# BUJT13-VN02-20140328.net
KiCad netlist of a schematic drawn in Altium Designer
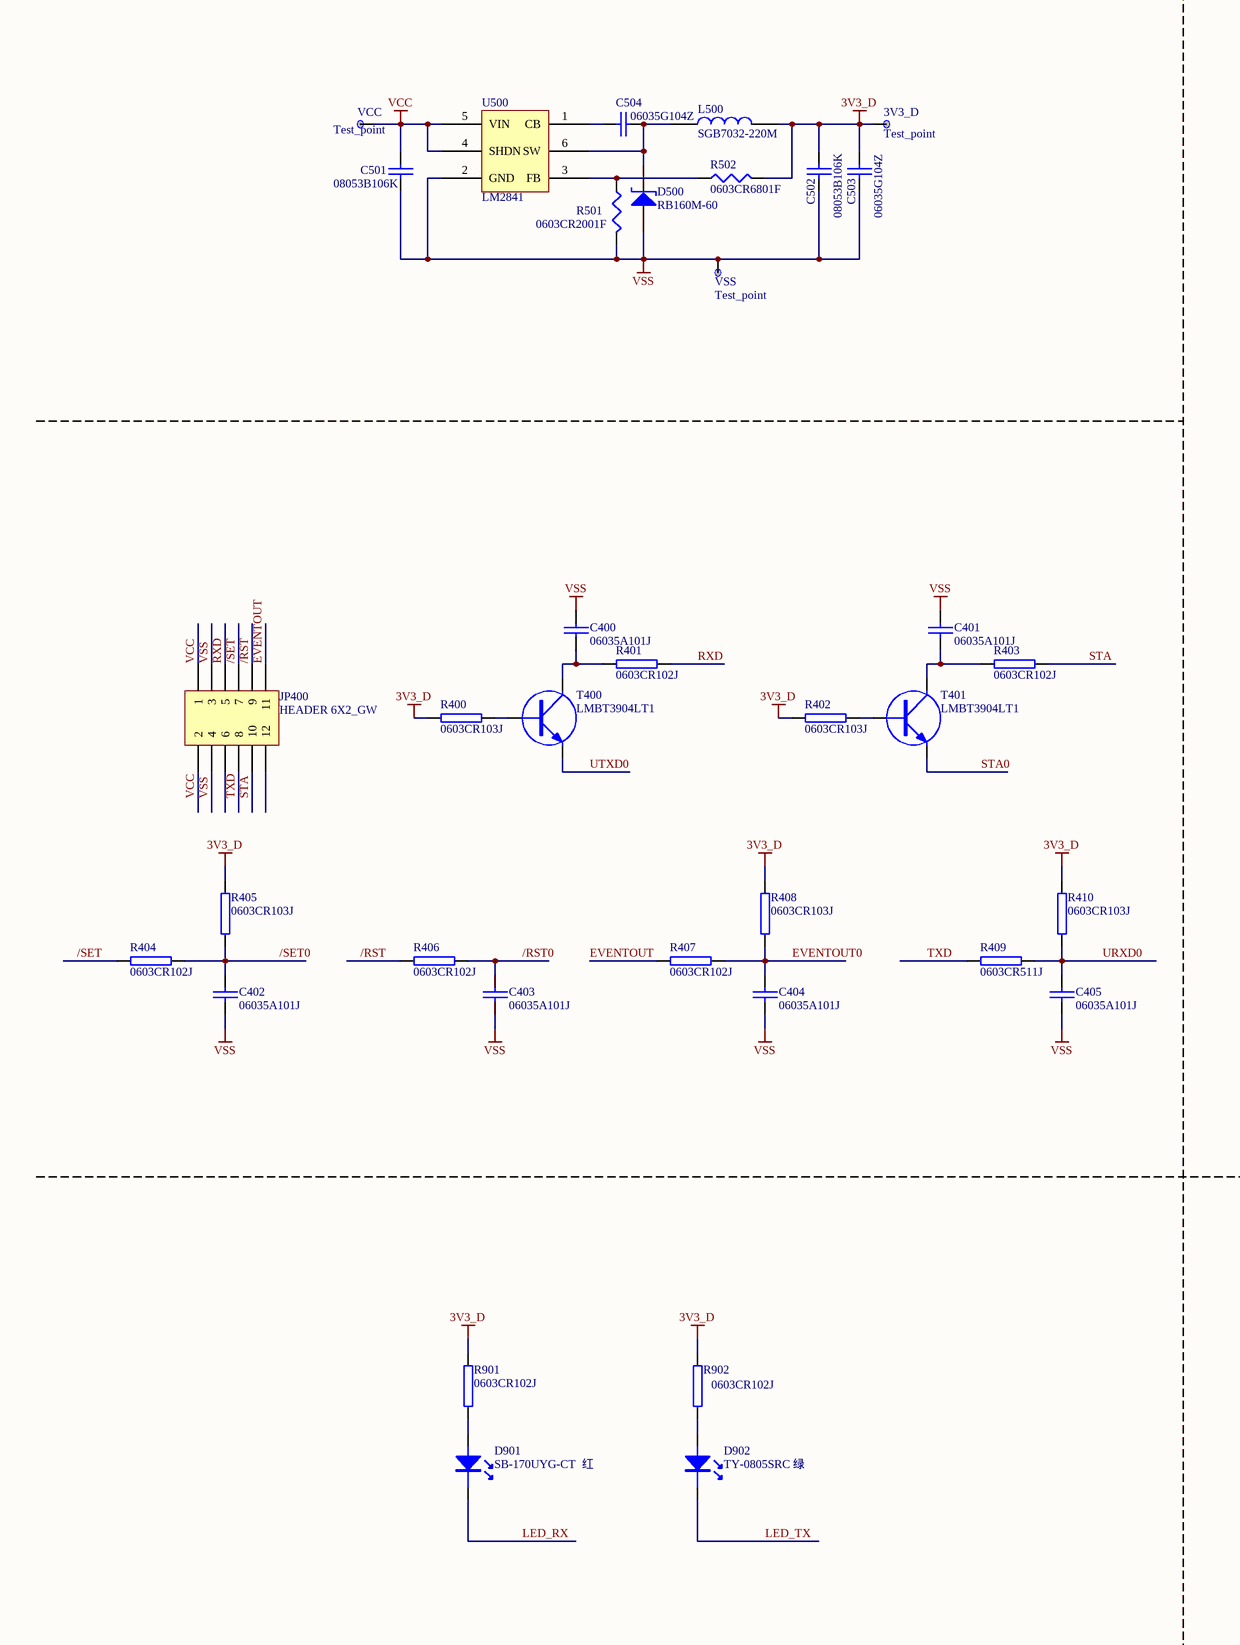
[diagram p0: BUJT13-VN02-20140328.SchDoc, left]
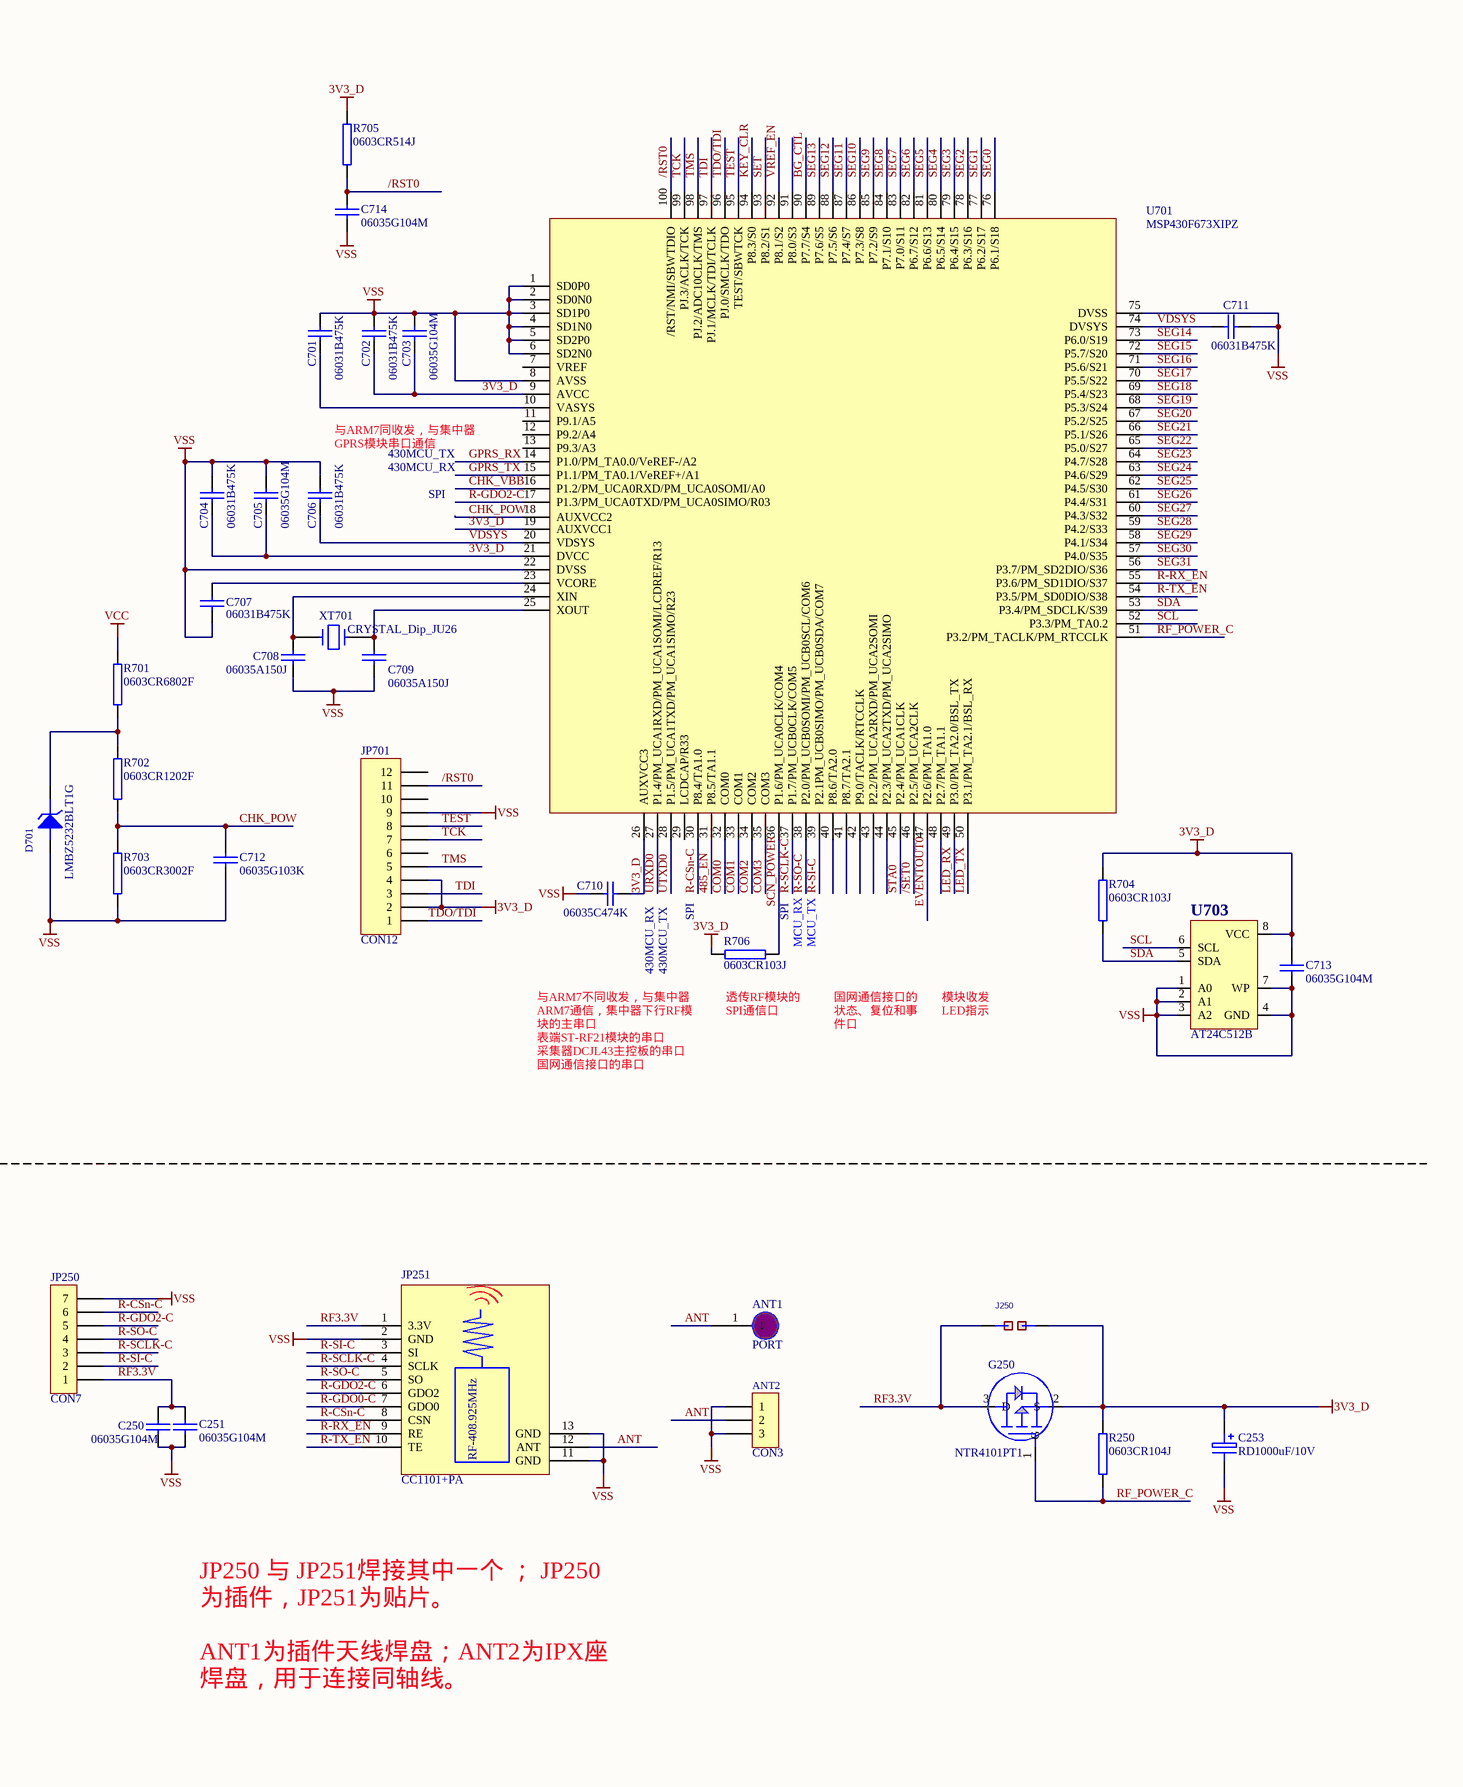
[diagram p1: BUJT13-VN02-20140328.SchDoc, right]

(export (version "E")
  (design (tool "Eeschema 10.0.6"))
  (components
    (comp (ref "3V3_D")
      (value "Test_point")
      (footprint "test_port")
      (libsource (lib "STAR_SCHLIB") (part "Test_point"))
    )
    (comp (ref "ANT1") (value "PORT") (footprint "ANT1") (libsource (lib "STAR_SCHLIB") (part "PORT")))
    (comp (ref "ANT2")
      (value "CON3")
      (footprint "RF_IPX")
      (description "Connector")
      (libsource (lib "STAR_SCHLIB") (part "CON3"))
    )
    (comp (ref "C250") (value "06035G104M") (footprint "0603C") (libsource (lib "STAR_SCHLIB") (part "CAP")))
    (comp (ref "C251") (value "06035G104M") (footprint "0603C") (libsource (lib "STAR_SCHLIB") (part "CAP")))
    (comp (ref "C253")
      (value "RD1000uF/10V")
      (footprint "CAP_ALU10.0_5.0_DOWN")
      (description "Electrolytic Capacitor")
      (libsource (lib "STAR_SCHLIB") (part "CA45 10uF/M 16V"))
    )
    (comp (ref "C400") (value "06035A101J") (footprint "0603C") (libsource (lib "STAR_SCHLIB") (part "CAP")))
    (comp (ref "C401") (value "06035A101J") (footprint "0603C") (libsource (lib "STAR_SCHLIB") (part "CAP")))
    (comp (ref "C402") (value "06035A101J") (footprint "0603C") (libsource (lib "STAR_SCHLIB") (part "CAP")))
    (comp (ref "C403") (value "06035A101J") (footprint "0603C") (libsource (lib "STAR_SCHLIB") (part "CAP")))
    (comp (ref "C404") (value "06035A101J") (footprint "0603C") (libsource (lib "STAR_SCHLIB") (part "CAP")))
    (comp (ref "C405") (value "06035A101J") (footprint "0603C") (libsource (lib "STAR_SCHLIB") (part "CAP")))
    (comp (ref "C501") (value "08053B106K") (footprint "0805C") (libsource (lib "STAR_SCHLIB") (part "CAP")))
    (comp (ref "C502") (value "08053B106K") (footprint "0805C") (libsource (lib "STAR_SCHLIB") (part "CAP")))
    (comp (ref "C503") (value "06035G104Z") (footprint "0603C") (libsource (lib "STAR_SCHLIB") (part "CAP")))
    (comp (ref "C504") (value "06035G104Z") (footprint "0603C") (libsource (lib "STAR_SCHLIB") (part "CAP")))
    (comp (ref "C701") (value "06031B475K") (footprint "0603C") (libsource (lib "STAR_SCHLIB") (part "CAP")))
    (comp (ref "C702") (value "06031B475K") (footprint "0603C") (libsource (lib "STAR_SCHLIB") (part "CAP")))
    (comp (ref "C703") (value "06035G104M") (footprint "0603C") (libsource (lib "STAR_SCHLIB") (part "CAP")))
    (comp (ref "C704") (value "06031B475K") (footprint "0603C") (libsource (lib "STAR_SCHLIB") (part "CAP")))
    (comp (ref "C705") (value "06035G104M") (footprint "0603C") (libsource (lib "STAR_SCHLIB") (part "CAP")))
    (comp (ref "C706") (value "06031B475K") (footprint "0603C") (libsource (lib "STAR_SCHLIB") (part "CAP")))
    (comp (ref "C707") (value "06031B475K") (footprint "0603C") (libsource (lib "STAR_SCHLIB") (part "CAP")))
    (comp (ref "C708") (value "06035A150J") (footprint "0603C") (libsource (lib "STAR_SCHLIB") (part "CAP")))
    (comp (ref "C709") (value "06035A150J") (footprint "0603C") (libsource (lib "STAR_SCHLIB") (part "CAP")))
    (comp (ref "C710") (value "06035C474K") (footprint "0603C") (libsource (lib "STAR_SCHLIB") (part "CAP")))
    (comp (ref "C711") (value "06031B475K") (footprint "0603C") (libsource (lib "STAR_SCHLIB") (part "CAP")))
    (comp (ref "C712") (value "06035G103K") (footprint "0603C") (libsource (lib "STAR_SCHLIB") (part "CAP")))
    (comp (ref "C713") (value "06035G104M") (footprint "0603C") (libsource (lib "STAR_SCHLIB") (part "CAP")))
    (comp (ref "C714") (value "06035G104M") (footprint "0603C") (libsource (lib "STAR_SCHLIB") (part "CAP")))
    (comp (ref "D500")
      (value "RB160M-60")
      (footprint "RB160M")
      (libsource (lib "STAR_SCHLIB") (part "RB160M-60"))
    )
    (comp (ref "D701")
      (value "LMBZ5232BLT1G")
      (footprint "LMBZ5230BLT1G")
      (description "Zener Diode")
      (libsource (lib "STAR_SCHLIB") (part "ZENER3_7"))
    )
    (comp (ref "D901")
      (value "SB-170UYG-CT  红")
      (footprint "0805-LED")
      (libsource (lib "STAR_SCHLIB") (part "LED_5"))
    )
    (comp (ref "D902")
      (value "TY-0805SRC 绿")
      (footprint "0805-LED")
      (libsource (lib "STAR_SCHLIB") (part "LED_5"))
    )
    (comp (ref "G250")
      (value "NTR4101PT1")
      (footprint "SOT-23")
      (description "MOSFET_P")
      (libsource (lib "STAR_SCHLIB") (part "MOSFET_P"))
    )
    (comp (ref "J250") (value "JUMP-0603 NC") (libsource (lib "STAR_SCHLIB") (part "GDC_NO-0603")))
    (comp (ref "JP250")
      (value "CON7")
      (footprint "RF_CC1101-1-NOANT")
      (description "Connector")
      (libsource (lib "STAR_SCHLIB") (part "CON7"))
    )
    (comp (ref "JP251")
      (value "CC1101+PA")
      (footprint "CC1101-S-PA")
      (libsource (lib "STAR_SCHLIB") (part "CC1101+PA"))
    )
    (comp (ref "JP400")
      (value "HEADER 6X2_GW")
      (footprint "IDC12G_GW")
      (libsource (lib "STAR_SCHLIB") (part "HEADER 6X2_GW"))
    )
    (comp (ref "JP701")
      (value "CON12")
      (footprint "IDC12G")
      (description "Connector")
      (libsource (lib "STAR_SCHLIB") (part "CON12"))
    )
    (comp (ref "L500")
      (value "SGB7032-220M")
      (footprint "SGB7032")
      (libsource (lib "STAR_SCHLIB") (part "SGB7032-220M"))
    )
    (comp (ref "R250") (value "0603CR104J") (footprint "0603R") (libsource (lib "STAR_SCHLIB") (part "RES2")))
    (comp (ref "R400")
      (value "0603CR103J")
      (footprint "0603R")
      (libsource (lib "STAR_SCHLIB") (part "RES2_0603"))
    )
    (comp (ref "R401")
      (value "0603CR102J")
      (footprint "0603R")
      (libsource (lib "STAR_SCHLIB") (part "RES2_0603"))
    )
    (comp (ref "R402")
      (value "0603CR103J")
      (footprint "0603R")
      (libsource (lib "STAR_SCHLIB") (part "RES2_0603"))
    )
    (comp (ref "R403")
      (value "0603CR102J")
      (footprint "0603R")
      (libsource (lib "STAR_SCHLIB") (part "RES2_0603"))
    )
    (comp (ref "R404")
      (value "0603CR102J")
      (footprint "0603R")
      (libsource (lib "STAR_SCHLIB") (part "RES2_0603"))
    )
    (comp (ref "R405")
      (value "0603CR103J")
      (footprint "0603R")
      (libsource (lib "STAR_SCHLIB") (part "RES2_0603"))
    )
    (comp (ref "R406")
      (value "0603CR102J")
      (footprint "0603R")
      (libsource (lib "STAR_SCHLIB") (part "RES2_0603"))
    )
    (comp (ref "R407")
      (value "0603CR102J")
      (footprint "0603R")
      (libsource (lib "STAR_SCHLIB") (part "RES2_0603"))
    )
    (comp (ref "R408")
      (value "0603CR103J")
      (footprint "0603R")
      (libsource (lib "STAR_SCHLIB") (part "RES2_0603"))
    )
    (comp (ref "R409")
      (value "0603CR511J")
      (footprint "0603R")
      (libsource (lib "STAR_SCHLIB") (part "RES2_0603"))
    )
    (comp (ref "R410")
      (value "0603CR103J")
      (footprint "0603R")
      (libsource (lib "STAR_SCHLIB") (part "RES2_0603"))
    )
    (comp (ref "R501")
      (value "0603CR2001F")
      (footprint "0603R")
      (libsource (lib "STAR_SCHLIB") (part "RES1"))
    )
    (comp (ref "R502")
      (value "0603CR6801F")
      (footprint "0603R")
      (libsource (lib "STAR_SCHLIB") (part "RES1"))
    )
    (comp (ref "R701")
      (value "0603CR6802F")
      (footprint "0603R")
      (libsource (lib "STAR_SCHLIB") (part "RES2"))
    )
    (comp (ref "R702")
      (value "0603CR1202F")
      (footprint "0603R")
      (libsource (lib "STAR_SCHLIB") (part "RES2"))
    )
    (comp (ref "R703")
      (value "0603CR3002F")
      (footprint "0603R")
      (libsource (lib "STAR_SCHLIB") (part "RES2"))
    )
    (comp (ref "R704") (value "0603CR103J") (footprint "0603R") (libsource (lib "STAR_SCHLIB") (part "RES2")))
    (comp (ref "R705") (value "0603CR514J") (footprint "0603R") (libsource (lib "STAR_SCHLIB") (part "RES2")))
    (comp (ref "R706") (value "0603CR103J") (footprint "0603R") (libsource (lib "STAR_SCHLIB") (part "RES2")))
    (comp (ref "R901") (value "0603CR102J") (footprint "0603R") (libsource (lib "STAR_SCHLIB") (part "RES2")))
    (comp (ref "R902") (value "0603CR102J") (footprint "0603R") (libsource (lib "STAR_SCHLIB") (part "RES2")))
    (comp (ref "T400")
      (value "LMBT3904LT1")
      (footprint "SOT-23")
      (libsource (lib "STAR_SCHLIB") (part "NPN"))
    )
    (comp (ref "T401")
      (value "LMBT3904LT1")
      (footprint "SOT-23")
      (libsource (lib "STAR_SCHLIB") (part "NPN"))
    )
    (comp (ref "U500")
      (value "LM2841")
      (footprint "SOT-23-6L")
      (libsource (lib "STAR_SCHLIB") (part "LM2841"))
    )
    (comp (ref "U701")
      (value "MSP430F673XIPZ")
      (footprint "LQFP100 - 1")
      (libsource (lib "STAR_SCHLIB") (part "MSP430F673XIPZ"))
    )
    (comp (ref "U703") (value "AT24C512B") (footprint "SOP-8") (libsource (lib "STAR_SCHLIB") (part "24C01")))
    (comp (ref "VCC")
      (value "Test_point")
      (footprint "test_port")
      (libsource (lib "STAR_SCHLIB") (part "Test_point"))
    )
    (comp (ref "VSS")
      (value "Test_point")
      (footprint "test_port")
      (libsource (lib "STAR_SCHLIB") (part "Test_point"))
    )
    (comp (ref "XT701")
      (value "CRYSTAL_Dip_JU26")
      (footprint "XTAL-DIP-JU26")
      (description "Crystal")
      (libsource (lib "STAR_SCHLIB") (part "CRYSTAL_Dip_JU26"))
    )
  )
  (nets
    (net (code "1") (name "/485_EN") (class "Default")
      (node (ref "U701") (pin "31") (pinfunction "P8.5/TA1.1_31") (pintype "passive"))
    )
    (net (code "2") (name "/ANT") (class "Default")
      (node (ref "ANT1") (pin "1") (pinfunction "1_1") (pintype "passive"))
      (node (ref "ANT2") (pin "2") (pinfunction "2_2") (pintype "passive"))
      (node (ref "JP251") (pin "12") (pinfunction "ANT_12") (pintype "passive"))
    )
    (net (code "3") (name "/BG_CTL") (class "Default")
      (node (ref "U701") (pin "90") (pinfunction "P7.7/S4_90") (pintype "passive"))
    )
    (net (code "4") (name "/CHK_POW") (class "Default")
      (node (ref "C712") (pin "1") (pintype "passive"))
      (node (ref "R702") (pin "1") (pintype "passive"))
      (node (ref "R703") (pin "2") (pintype "passive"))
      (node (ref "U701") (pin "18") (pinfunction "AUXVCC2_18") (pintype "passive"))
    )
    (net (code "5") (name "/CHK_VBB") (class "Default")
      (node (ref "U701") (pin "16") (pinfunction "P1.2/PM_UCA0RXD/PM_UCA0SOMI/A0_16") (pintype "passive"))
    )
    (net (code "6") (name "/COM0") (class "Default")
      (node (ref "U701") (pin "32") (pinfunction "COM0_32") (pintype "passive"))
    )
    (net (code "7") (name "/COM1") (class "Default")
      (node (ref "U701") (pin "33") (pinfunction "COM1_33") (pintype "passive"))
    )
    (net (code "8") (name "/COM2") (class "Default")
      (node (ref "U701") (pin "34") (pinfunction "COM2_34") (pintype "passive"))
    )
    (net (code "9") (name "/COM3") (class "Default")
      (node (ref "U701") (pin "35") (pinfunction "COM3_35") (pintype "passive"))
    )
    (net (code "10") (name "/EVENTOUT") (class "Default")
      (node (ref "JP400") (pin "11") (pinfunction "11_11") (pintype "passive"))
      (node (ref "R407") (pin "2") (pintype "passive"))
    )
    (net (code "11") (name "/EVENTOUT0") (class "Default")
      (node (ref "C404") (pin "1") (pintype "passive"))
      (node (ref "R407") (pin "1") (pintype "passive"))
      (node (ref "R408") (pin "2") (pintype "passive"))
      (node (ref "U701") (pin "47") (pinfunction "P2.6/PM_TA1.0_47") (pintype "passive"))
    )
    (net (code "12") (name "/GPRS_RX") (class "Default")
      (node (ref "U701") (pin "14") (pinfunction "P1.0/PM_TA0.0/VeREF-/A2_14") (pintype "passive"))
    )
    (net (code "13") (name "/GPRS_TX") (class "Default")
      (node (ref "U701") (pin "15") (pinfunction "P1.1/PM_TA0.1/VeREF+/A1_15") (pintype "passive"))
    )
    (net (code "14") (name "/KEY_CLR") (class "Default")
      (node (ref "U701") (pin "94") (pinfunction "P8.3/S0_94") (pintype "passive"))
    )
    (net (code "15") (name "/LED_RX") (class "Default")
      (node (ref "D901") (pin "K") (pintype "passive"))
      (node (ref "U701") (pin "49") (pinfunction "P3.0/PM_TA2.0/BSL_TX_49") (pintype "passive"))
    )
    (net (code "16") (name "/LED_TX") (class "Default")
      (node (ref "D902") (pin "K") (pintype "passive"))
      (node (ref "U701") (pin "50") (pinfunction "P3.1/PM_TA2.1/BSL_RX_50") (pintype "passive"))
    )
    (net (code "17") (name "/R-CSn-C") (class "Default")
      (node (ref "JP250") (pin "6") (pinfunction "6_6") (pintype "passive"))
      (node (ref "JP251") (pin "8") (pinfunction "CSN_8") (pintype "passive"))
      (node (ref "U701") (pin "30") (pinfunction "P8.4/TA1.0_30") (pintype "passive"))
    )
    (net (code "18") (name "/R-GDO0-C") (class "Default")
      (node (ref "JP251") (pin "7") (pinfunction "GDO0_7") (pintype "passive"))
    )
    (net (code "19") (name "/R-GDO2-C") (class "Default")
      (node (ref "JP250") (pin "5") (pinfunction "5_5") (pintype "passive"))
      (node (ref "JP251") (pin "6") (pinfunction "GDO2_6") (pintype "passive"))
      (node (ref "U701") (pin "17") (pinfunction "P1.3/PM_UCA0TXD/PM_UCA0SIMO/R03_17") (pintype "passive"))
    )
    (net (code "20") (name "/R-RX_EN") (class "Default")
      (node (ref "JP251") (pin "9") (pinfunction "RE_9") (pintype "passive"))
      (node (ref "U701") (pin "55") (pinfunction "P3.6/PM_SD1DIO/S37_55") (pintype "passive"))
    )
    (net (code "21") (name "/R-SCLK-C") (class "Default")
      (node (ref "JP250") (pin "3") (pinfunction "3_3") (pintype "passive"))
      (node (ref "JP251") (pin "4") (pinfunction "SCLK_4") (pintype "passive"))
      (node (ref "U701") (pin "37") (pinfunction "P1.7/PM_UCB0CLK/COM5_37") (pintype "passive"))
    )
    (net (code "22") (name "/R-SI-C") (class "Default")
      (node (ref "JP250") (pin "2") (pinfunction "2_2") (pintype "passive"))
      (node (ref "JP251") (pin "3") (pinfunction "SI_3") (pintype "passive"))
      (node (ref "U701") (pin "39") (pinfunction "P2.1PM_UCB0SIMO/PM_UCB0SDA/COM7_39") (pintype "passive"))
    )
    (net (code "23") (name "/R-SO-C") (class "Default")
      (node (ref "JP250") (pin "4") (pinfunction "4_4") (pintype "passive"))
      (node (ref "JP251") (pin "5") (pinfunction "SO_5") (pintype "passive"))
      (node (ref "U701") (pin "38") (pinfunction "P2.0/PM_UCB0SOMI/PM_UCB0SCL/COM6_38") (pintype "passive"))
    )
    (net (code "24") (name "/R-TX_EN") (class "Default")
      (node (ref "JP251") (pin "10") (pinfunction "TE_10") (pintype "passive"))
      (node (ref "U701") (pin "54") (pinfunction "P3.5/PM_SD0DIO/S38_54") (pintype "passive"))
    )
    (net (code "25") (name "/RF3.3V") (class "Default")
      (node (ref "C250") (pin "1") (pintype "passive"))
      (node (ref "C251") (pin "1") (pintype "passive"))
      (node (ref "G250") (pin "3") (pinfunction "D_3") (pintype "passive"))
      (node (ref "J250") (pin "2") (pinfunction "R2_2") (pintype "passive"))
      (node (ref "JP250") (pin "1") (pinfunction "1_1") (pintype "passive"))
      (node (ref "JP251") (pin "1") (pinfunction "3.3V_1") (pintype "passive"))
    )
    (net (code "26") (name "/RF_POWER_C") (class "Default")
      (node (ref "G250") (pin "1") (pinfunction "G_1") (pintype "passive"))
      (node (ref "R250") (pin "2") (pintype "passive"))
      (node (ref "U701") (pin "51") (pinfunction "P3.2/PM_TACLK/PM_RTCCLK_51") (pintype "passive"))
    )
    (net (code "27") (name "/RXD") (class "Default")
      (node (ref "JP400") (pin "5") (pinfunction "5_5") (pintype "passive"))
      (node (ref "R401") (pin "2") (pintype "passive"))
    )
    (net (code "28") (name "/SCL") (class "Default")
      (node (ref "U701") (pin "52") (pinfunction "P3.3/PM_TA0.2_52") (pintype "passive"))
      (node (ref "U703") (pin "6") (pinfunction "SCL_6") (pintype "passive"))
    )
    (net (code "29") (name "/SCN_POWER") (class "Default")
      (node (ref "R706") (pin "2") (pintype "passive"))
      (node (ref "U701") (pin "36") (pinfunction "P1.6/PM_UCA0CLK/COM4_36") (pintype "passive"))
    )
    (net (code "30") (name "/SDA") (class "Default")
      (node (ref "R704") (pin "1") (pintype "passive"))
      (node (ref "U701") (pin "53") (pinfunction "P3.4/PM_SDCLK/S39_53") (pintype "passive"))
      (node (ref "U703") (pin "5") (pinfunction "SDA_5") (pintype "passive"))
    )
    (net (code "31") (name "/SEG0") (class "Default")
      (node (ref "U701") (pin "76") (pinfunction "P6.1/S18_76") (pintype "passive"))
    )
    (net (code "32") (name "/SEG1") (class "Default")
      (node (ref "U701") (pin "77") (pinfunction "P6.2/S17_77") (pintype "passive"))
    )
    (net (code "33") (name "/SEG2") (class "Default")
      (node (ref "U701") (pin "78") (pinfunction "P6.3/S16_78") (pintype "passive"))
    )
    (net (code "34") (name "/SEG3") (class "Default")
      (node (ref "U701") (pin "79") (pinfunction "P6.4/S15_79") (pintype "passive"))
    )
    (net (code "35") (name "/SEG4") (class "Default")
      (node (ref "U701") (pin "80") (pinfunction "P6.5/S14_80") (pintype "passive"))
    )
    (net (code "36") (name "/SEG5") (class "Default")
      (node (ref "U701") (pin "81") (pinfunction "P6.6/S13_81") (pintype "passive"))
    )
    (net (code "37") (name "/SEG6") (class "Default")
      (node (ref "U701") (pin "82") (pinfunction "P6.7/S12_82") (pintype "passive"))
    )
    (net (code "38") (name "/SEG7") (class "Default")
      (node (ref "U701") (pin "83") (pinfunction "P7.0/S11_83") (pintype "passive"))
    )
    (net (code "39") (name "/SEG8") (class "Default")
      (node (ref "U701") (pin "84") (pinfunction "P7.1/S10_84") (pintype "passive"))
    )
    (net (code "40") (name "/SEG9") (class "Default")
      (node (ref "U701") (pin "85") (pinfunction "P7.2/S9_85") (pintype "passive"))
    )
    (net (code "41") (name "/SEG10") (class "Default")
      (node (ref "U701") (pin "86") (pinfunction "P7.3/S8_86") (pintype "passive"))
    )
    (net (code "42") (name "/SEG11") (class "Default")
      (node (ref "U701") (pin "87") (pinfunction "P7.4/S7_87") (pintype "passive"))
    )
    (net (code "43") (name "/SEG12") (class "Default")
      (node (ref "U701") (pin "88") (pinfunction "P7.5/S6_88") (pintype "passive"))
    )
    (net (code "44") (name "/SEG13") (class "Default")
      (node (ref "U701") (pin "89") (pinfunction "P7.6/S5_89") (pintype "passive"))
    )
    (net (code "45") (name "/SEG14") (class "Default")
      (node (ref "U701") (pin "73") (pinfunction "P6.0/S19_73") (pintype "passive"))
    )
    (net (code "46") (name "/SEG15") (class "Default")
      (node (ref "U701") (pin "72") (pinfunction "P5.7/S20_72") (pintype "passive"))
    )
    (net (code "47") (name "/SEG16") (class "Default")
      (node (ref "U701") (pin "71") (pinfunction "P5.6/S21_71") (pintype "passive"))
    )
    (net (code "48") (name "/SEG17") (class "Default")
      (node (ref "U701") (pin "70") (pinfunction "P5.5/S22_70") (pintype "passive"))
    )
    (net (code "49") (name "/SEG18") (class "Default")
      (node (ref "U701") (pin "69") (pinfunction "P5.4/S23_69") (pintype "passive"))
    )
    (net (code "50") (name "/SEG19") (class "Default")
      (node (ref "U701") (pin "68") (pinfunction "P5.3/S24_68") (pintype "passive"))
    )
    (net (code "51") (name "/SEG20") (class "Default")
      (node (ref "U701") (pin "67") (pinfunction "P5.2/S25_67") (pintype "passive"))
    )
    (net (code "52") (name "/SEG21") (class "Default")
      (node (ref "U701") (pin "66") (pinfunction "P5.1/S26_66") (pintype "passive"))
    )
    (net (code "53") (name "/SEG22") (class "Default")
      (node (ref "U701") (pin "65") (pinfunction "P5.0/S27_65") (pintype "passive"))
    )
    (net (code "54") (name "/SEG23") (class "Default")
      (node (ref "U701") (pin "64") (pinfunction "P4.7/S28_64") (pintype "passive"))
    )
    (net (code "55") (name "/SEG24") (class "Default")
      (node (ref "U701") (pin "63") (pinfunction "P4.6/S29_63") (pintype "passive"))
    )
    (net (code "56") (name "/SEG25") (class "Default")
      (node (ref "U701") (pin "62") (pinfunction "P4.5/S30_62") (pintype "passive"))
    )
    (net (code "57") (name "/SEG26") (class "Default")
      (node (ref "U701") (pin "61") (pinfunction "P4.4/S31_61") (pintype "passive"))
    )
    (net (code "58") (name "/SEG27") (class "Default")
      (node (ref "U701") (pin "60") (pinfunction "P4.3/S32_60") (pintype "passive"))
    )
    (net (code "59") (name "/SEG28") (class "Default")
      (node (ref "U701") (pin "59") (pinfunction "P4.2/S33_59") (pintype "passive"))
    )
    (net (code "60") (name "/SEG29") (class "Default")
      (node (ref "U701") (pin "58") (pinfunction "P4.1/S34_58") (pintype "passive"))
    )
    (net (code "61") (name "/SEG30") (class "Default")
      (node (ref "U701") (pin "57") (pinfunction "P4.0/S35_57") (pintype "passive"))
    )
    (net (code "62") (name "/SEG31") (class "Default")
      (node (ref "U701") (pin "56") (pinfunction "P3.7/PM_SD2DIO/S36_56") (pintype "passive"))
    )
    (net (code "63") (name "/SET") (class "Default")
      (node (ref "U701") (pin "93") (pinfunction "P8.2/S1_93") (pintype "passive"))
    )
    (net (code "64") (name "/STA") (class "Default")
      (node (ref "JP400") (pin "10") (pinfunction "10_10") (pintype "passive"))
      (node (ref "R403") (pin "2") (pintype "passive"))
    )
    (net (code "65") (name "/STA0") (class "Default")
      (node (ref "T401") (pin "2") (pinfunction "E_2") (pintype "passive"))
      (node (ref "U701") (pin "45") (pinfunction "P2.4/PM_UCA1CLK_45") (pintype "passive"))
    )
    (net (code "66") (name "/TCK") (class "Default")
      (node (ref "JP701") (pin "7") (pinfunction "7_7") (pintype "passive"))
      (node (ref "U701") (pin "99") (pinfunction "PJ.3/ACLK/TCK_99") (pintype "passive"))
    )
    (net (code "67") (name "/TDI") (class "Default")
      (node (ref "JP701") (pin "3") (pinfunction "3_3") (pintype "passive"))
      (node (ref "U701") (pin "97") (pinfunction "PJ.1/MCLK/TDI/TCLK_97") (pintype "passive"))
    )
    (net (code "68") (name "/TDO{slash}TDI") (class "Default")
      (node (ref "JP701") (pin "1") (pinfunction "1_1") (pintype "passive"))
      (node (ref "U701") (pin "96") (pinfunction "PJ.0/SMCLK/TDO_96") (pintype "passive"))
    )
    (net (code "69") (name "/TEST") (class "Default")
      (node (ref "JP701") (pin "8") (pinfunction "8_8") (pintype "passive"))
      (node (ref "U701") (pin "95") (pinfunction "TEST/SBWTCK_95") (pintype "passive"))
    )
    (net (code "70") (name "/TMS") (class "Default")
      (node (ref "JP701") (pin "5") (pinfunction "5_5") (pintype "passive"))
      (node (ref "U701") (pin "98") (pinfunction "PJ.2/ADC10CLK/TMS_98") (pintype "passive"))
    )
    (net (code "71") (name "/TXD") (class "Default")
      (node (ref "JP400") (pin "8") (pinfunction "8_8") (pintype "passive"))
      (node (ref "R409") (pin "1") (pintype "passive"))
    )
    (net (code "72") (name "/URXD0") (class "Default")
      (node (ref "C405") (pin "1") (pintype "passive"))
      (node (ref "R409") (pin "2") (pintype "passive"))
      (node (ref "R410") (pin "1") (pintype "passive"))
      (node (ref "U701") (pin "27") (pinfunction "P1.4/PM_UCA1RXD/PM_UCA1SOMI/LCDREF/R13_27") (pintype "passive"))
    )
    (net (code "73") (name "/UTXD0") (class "Default")
      (node (ref "T400") (pin "2") (pinfunction "E_2") (pintype "passive"))
      (node (ref "U701") (pin "28") (pinfunction "P1.5/PM_UCA1TXD/PM_UCA1SIMO/R23_28") (pintype "passive"))
    )
    (net (code "74") (name "/VDSYS") (class "Default")
      (node (ref "C706") (pin "2") (pintype "passive"))
      (node (ref "C711") (pin "1") (pintype "passive"))
      (node (ref "U701") (pin "20") (pinfunction "VDSYS_20") (pintype "passive"))
      (node (ref "U701") (pin "74") (pinfunction "DVSYS_74") (pintype "passive"))
    )
    (net (code "75") (name "/VREF_EN") (class "Default")
      (node (ref "U701") (pin "92") (pinfunction "P8.1/S2_92") (pintype "passive"))
    )
    (net (code "76") (name "/{slash}RST") (class "Default")
      (node (ref "JP400") (pin "9") (pinfunction "9_9") (pintype "passive"))
      (node (ref "R406") (pin "2") (pintype "passive"))
    )
    (net (code "77") (name "/{slash}RST0") (class "Default")
      (node (ref "C403") (pin "1") (pintype "passive"))
      (node (ref "C714") (pin "1") (pintype "passive"))
      (node (ref "JP701") (pin "11") (pinfunction "11_11") (pintype "passive"))
      (node (ref "R406") (pin "1") (pintype "passive"))
      (node (ref "R705") (pin "1") (pintype "passive"))
      (node (ref "U701") (pin "100") (pinfunction "/RST/NMI/SBWTDIO_100") (pintype "passive"))
    )
    (net (code "78") (name "/{slash}SET") (class "Default")
      (node (ref "JP400") (pin "7") (pinfunction "7_7") (pintype "passive"))
      (node (ref "R404") (pin "1") (pintype "passive"))
    )
    (net (code "79") (name "/{slash}SET0") (class "Default")
      (node (ref "C402") (pin "1") (pintype "passive"))
      (node (ref "R404") (pin "2") (pintype "passive"))
      (node (ref "R405") (pin "1") (pintype "passive"))
      (node (ref "U701") (pin "46") (pinfunction "P2.5/PM_UCA2CLK_46") (pintype "passive"))
    )
    (net (code "80") (name "3V3_D") (class "Default")
      (node (ref "3V3_D") (pin "1") (pinfunction "1_1") (pintype "passive"))
      (node (ref "C253") (pin "1") (pinfunction "1_1") (pintype "passive"))
      (node (ref "C502") (pin "1") (pintype "passive"))
      (node (ref "C503") (pin "2") (pintype "passive"))
      (node (ref "C702") (pin "2") (pintype "passive"))
      (node (ref "C703") (pin "2") (pintype "passive"))
      (node (ref "C704") (pin "2") (pintype "passive"))
      (node (ref "C705") (pin "2") (pintype "passive"))
      (node (ref "C710") (pin "2") (pintype "passive"))
      (node (ref "C713") (pin "1") (pintype "passive"))
      (node (ref "G250") (pin "2") (pinfunction "S_2") (pintype "passive"))
      (node (ref "J250") (pin "1") (pinfunction "R1_1") (pintype "passive"))
      (node (ref "JP701") (pin "2") (pinfunction "2_2") (pintype "passive"))
      (node (ref "JP701") (pin "4") (pinfunction "4_4") (pintype "passive"))
      (node (ref "L500") (pin "2") (pinfunction "2_2") (pintype "passive"))
      (node (ref "R250") (pin "1") (pintype "passive"))
      (node (ref "R400") (pin "1") (pintype "passive"))
      (node (ref "R402") (pin "1") (pintype "passive"))
      (node (ref "R405") (pin "2") (pintype "passive"))
      (node (ref "R408") (pin "1") (pintype "passive"))
      (node (ref "R410") (pin "2") (pintype "passive"))
      (node (ref "R502") (pin "2") (pinfunction "2_2") (pintype "passive"))
      (node (ref "R704") (pin "2") (pintype "passive"))
      (node (ref "R705") (pin "2") (pintype "passive"))
      (node (ref "R706") (pin "1") (pintype "passive"))
      (node (ref "R901") (pin "2") (pintype "passive"))
      (node (ref "R902") (pin "2") (pintype "passive"))
      (node (ref "U701") (pin "19") (pinfunction "AUXVCC1_19") (pintype "passive"))
      (node (ref "U701") (pin "21") (pinfunction "DVCC_21") (pintype "passive"))
      (node (ref "U701") (pin "26") (pinfunction "AUXVCC3_26") (pintype "passive"))
      (node (ref "U701") (pin "9") (pinfunction "AVCC_9") (pintype "passive"))
      (node (ref "U703") (pin "8") (pinfunction "VCC_8") (pintype "passive"))
    )
    (net (code "81") (name "Net-(D500-2)") (class "Default")
      (node (ref "C504") (pin "2") (pintype "passive"))
      (node (ref "D500") (pin "K") (pinfunction "2_K") (pintype "passive"))
      (node (ref "L500") (pin "1") (pinfunction "1_1") (pintype "passive"))
      (node (ref "U500") (pin "6") (pinfunction "SW_6") (pintype "passive"))
    )
    (net (code "82") (name "Net-(D701-PadK)") (class "Default")
      (node (ref "D701") (pin "K") (pintype "passive"))
      (node (ref "R701") (pin "1") (pintype "passive"))
      (node (ref "R702") (pin "2") (pintype "passive"))
    )
    (net (code "83") (name "Net-(D901-PadA)") (class "Default")
      (node (ref "D901") (pin "A") (pintype "passive"))
      (node (ref "R901") (pin "1") (pintype "passive"))
    )
    (net (code "84") (name "Net-(D902-PadA)") (class "Default")
      (node (ref "D902") (pin "A") (pintype "passive"))
      (node (ref "R902") (pin "1") (pintype "passive"))
    )
    (net (code "85") (name "Net-(T400-B)") (class "Default")
      (node (ref "R400") (pin "2") (pintype "passive"))
      (node (ref "T400") (pin "1") (pinfunction "B_1") (pintype "passive"))
    )
    (net (code "86") (name "Net-(T400-C)") (class "Default")
      (node (ref "C400") (pin "2") (pintype "passive"))
      (node (ref "R401") (pin "1") (pintype "passive"))
      (node (ref "T400") (pin "3") (pinfunction "C_3") (pintype "passive"))
    )
    (net (code "87") (name "Net-(T401-B)") (class "Default")
      (node (ref "R402") (pin "2") (pintype "passive"))
      (node (ref "T401") (pin "1") (pinfunction "B_1") (pintype "passive"))
    )
    (net (code "88") (name "Net-(T401-C)") (class "Default")
      (node (ref "C401") (pin "2") (pintype "passive"))
      (node (ref "R403") (pin "1") (pintype "passive"))
      (node (ref "T401") (pin "3") (pinfunction "C_3") (pintype "passive"))
    )
    (net (code "89") (name "Net-(U500-CB)") (class "Default")
      (node (ref "C504") (pin "1") (pintype "passive"))
      (node (ref "U500") (pin "1") (pinfunction "CB_1") (pintype "passive"))
    )
    (net (code "90") (name "Net-(U500-FB)") (class "Default")
      (node (ref "R501") (pin "1") (pinfunction "1_1") (pintype "passive"))
      (node (ref "R502") (pin "1") (pinfunction "1_1") (pintype "passive"))
      (node (ref "U500") (pin "3") (pinfunction "FB_3") (pintype "passive"))
    )
    (net (code "91") (name "Net-(U701-VASYS)") (class "Default")
      (node (ref "C701") (pin "2") (pintype "passive"))
      (node (ref "U701") (pin "10") (pinfunction "VASYS_10") (pintype "passive"))
    )
    (net (code "92") (name "Net-(U701-VCORE)") (class "Default")
      (node (ref "C707") (pin "1") (pintype "passive"))
      (node (ref "U701") (pin "23") (pinfunction "VCORE_23") (pintype "passive"))
    )
    (net (code "93") (name "Net-(U701-XIN)") (class "Default")
      (node (ref "C708") (pin "1") (pintype "passive"))
      (node (ref "U701") (pin "24") (pinfunction "XIN_24") (pintype "passive"))
      (node (ref "XT701") (pin "1") (pinfunction "1_1") (pintype "passive"))
    )
    (net (code "94") (name "Net-(U701-XOUT)") (class "Default")
      (node (ref "C709") (pin "1") (pintype "passive"))
      (node (ref "U701") (pin "25") (pinfunction "XOUT_25") (pintype "passive"))
      (node (ref "XT701") (pin "2") (pinfunction "2_2") (pintype "passive"))
    )
    (net (code "95") (name "VCC") (class "Default")
      (node (ref "C501") (pin "1") (pintype "passive"))
      (node (ref "JP400") (pin "1") (pinfunction "1_1") (pintype "passive"))
      (node (ref "JP400") (pin "2") (pinfunction "2_2") (pintype "passive"))
      (node (ref "R701") (pin "2") (pintype "passive"))
      (node (ref "U500") (pin "4") (pinfunction "SHDN_4") (pintype "passive"))
      (node (ref "U500") (pin "5") (pinfunction "VIN_5") (pintype "passive"))
      (node (ref "VCC") (pin "1") (pinfunction "1_1") (pintype "passive"))
    )
    (net (code "96") (name "VSS") (class "Default")
      (node (ref "ANT2") (pin "1") (pinfunction "1_1") (pintype "passive"))
      (node (ref "ANT2") (pin "3") (pinfunction "3_3") (pintype "passive"))
      (node (ref "C250") (pin "2") (pintype "passive"))
      (node (ref "C251") (pin "2") (pintype "passive"))
      (node (ref "C253") (pin "2") (pinfunction "2_2") (pintype "passive"))
      (node (ref "C400") (pin "1") (pintype "passive"))
      (node (ref "C401") (pin "1") (pintype "passive"))
      (node (ref "C402") (pin "2") (pintype "passive"))
      (node (ref "C403") (pin "2") (pintype "passive"))
      (node (ref "C404") (pin "2") (pintype "passive"))
      (node (ref "C405") (pin "2") (pintype "passive"))
      (node (ref "C501") (pin "2") (pintype "passive"))
      (node (ref "C502") (pin "2") (pintype "passive"))
      (node (ref "C503") (pin "1") (pintype "passive"))
      (node (ref "C701") (pin "1") (pintype "passive"))
      (node (ref "C702") (pin "1") (pintype "passive"))
      (node (ref "C703") (pin "1") (pintype "passive"))
      (node (ref "C704") (pin "1") (pintype "passive"))
      (node (ref "C705") (pin "1") (pintype "passive"))
      (node (ref "C706") (pin "1") (pintype "passive"))
      (node (ref "C707") (pin "2") (pintype "passive"))
      (node (ref "C708") (pin "2") (pintype "passive"))
      (node (ref "C709") (pin "2") (pintype "passive"))
      (node (ref "C710") (pin "1") (pintype "passive"))
      (node (ref "C711") (pin "2") (pintype "passive"))
      (node (ref "C712") (pin "2") (pintype "passive"))
      (node (ref "C713") (pin "2") (pintype "passive"))
      (node (ref "C714") (pin "2") (pintype "passive"))
      (node (ref "D500") (pin "A") (pinfunction "1_A") (pintype "passive"))
      (node (ref "D701") (pin "A") (pintype "passive"))
      (node (ref "JP250") (pin "7") (pinfunction "7_7") (pintype "passive"))
      (node (ref "JP251") (pin "11") (pinfunction "GND_11") (pintype "passive"))
      (node (ref "JP251") (pin "13") (pinfunction "GND_13") (pintype "passive"))
      (node (ref "JP251") (pin "2") (pinfunction "GND_2") (pintype "passive"))
      (node (ref "JP400") (pin "3") (pinfunction "3_3") (pintype "passive"))
      (node (ref "JP400") (pin "4") (pinfunction "4_4") (pintype "passive"))
      (node (ref "JP701") (pin "9") (pinfunction "9_9") (pintype "passive"))
      (node (ref "R501") (pin "2") (pinfunction "2_2") (pintype "passive"))
      (node (ref "R703") (pin "1") (pintype "passive"))
      (node (ref "U500") (pin "2") (pinfunction "GND_2") (pintype "passive"))
      (node (ref "U701") (pin "1") (pinfunction "SD0P0_1") (pintype "passive"))
      (node (ref "U701") (pin "2") (pinfunction "SD0N0_2") (pintype "passive"))
      (node (ref "U701") (pin "22") (pinfunction "DVSS_22") (pintype "passive"))
      (node (ref "U701") (pin "3") (pinfunction "SD1P0_3") (pintype "passive"))
      (node (ref "U701") (pin "4") (pinfunction "SD1N0_4") (pintype "passive"))
      (node (ref "U701") (pin "5") (pinfunction "SD2P0_5") (pintype "passive"))
      (node (ref "U701") (pin "6") (pinfunction "SD2N0_6") (pintype "passive"))
      (node (ref "U701") (pin "75") (pinfunction "DVSS_75") (pintype "passive"))
      (node (ref "U701") (pin "8") (pinfunction "AVSS_8") (pintype "passive"))
      (node (ref "U703") (pin "1") (pinfunction "A0_1") (pintype "passive"))
      (node (ref "U703") (pin "2") (pinfunction "A1_2") (pintype "passive"))
      (node (ref "U703") (pin "3") (pinfunction "A2_3") (pintype "passive"))
      (node (ref "U703") (pin "4") (pinfunction "GND_4") (pintype "passive"))
      (node (ref "U703") (pin "7") (pinfunction "WP_7") (pintype "passive"))
      (node (ref "VSS") (pin "1") (pinfunction "1_1") (pintype "passive"))
    )
    (net (code "97") (name "unconnected-(JP400-Pad6)") (class "Default")
      (node (ref "JP400") (pin "6") (pinfunction "6_6") (pintype "passive"))
    )
    (net (code "98") (name "unconnected-(JP400-Pad12)") (class "Default")
      (node (ref "JP400") (pin "12") (pinfunction "12_12") (pintype "passive"))
    )
    (net (code "99") (name "unconnected-(JP701-Pad6)") (class "Default")
      (node (ref "JP701") (pin "6") (pinfunction "6_6") (pintype "passive"))
    )
    (net (code "100") (name "unconnected-(JP701-Pad10)") (class "Default")
      (node (ref "JP701") (pin "10") (pinfunction "10_10") (pintype "passive"))
    )
    (net (code "101") (name "unconnected-(JP701-Pad12)") (class "Default")
      (node (ref "JP701") (pin "12") (pinfunction "12_12") (pintype "passive"))
    )
    (net (code "102") (name "unconnected-(U701-LCDCAP{slash}R33-Pad29)") (class "Default")
      (node (ref "U701") (pin "29") (pinfunction "LCDCAP/R33_29") (pintype "passive"))
    )
    (net (code "103") (name "unconnected-(U701-P2.2{slash}PM_UCA2RXD{slash}PM_UCA2SOMI-Pad43)") (class "Default")
      (node (ref "U701") (pin "43") (pinfunction "P2.2/PM_UCA2RXD/PM_UCA2SOMI_43") (pintype "passive"))
    )
    (net (code "104") (name "unconnected-(U701-P2.3{slash}PM_UCA2TXD{slash}PM_UCA2SIMO-Pad44)") (class "Default")
      (node (ref "U701") (pin "44") (pinfunction "P2.3/PM_UCA2TXD/PM_UCA2SIMO_44") (pintype "passive"))
    )
    (net (code "105") (name "unconnected-(U701-P2.7{slash}PM_TA1.1-Pad48)") (class "Default")
      (node (ref "U701") (pin "48") (pinfunction "P2.7/PM_TA1.1_48") (pintype "passive"))
    )
    (net (code "106") (name "unconnected-(U701-P8.0{slash}S3-Pad91)") (class "Default")
      (node (ref "U701") (pin "91") (pinfunction "P8.0/S3_91") (pintype "passive"))
    )
    (net (code "107") (name "unconnected-(U701-P8.6{slash}TA2.0-Pad40)") (class "Default")
      (node (ref "U701") (pin "40") (pinfunction "P8.6/TA2.0_40") (pintype "passive"))
    )
    (net (code "108") (name "unconnected-(U701-P8.7{slash}TA2.1-Pad41)") (class "Default")
      (node (ref "U701") (pin "41") (pinfunction "P8.7/TA2.1_41") (pintype "passive"))
    )
    (net (code "109") (name "unconnected-(U701-P9.0{slash}TACLK{slash}RTCCLK-Pad42)") (class "Default")
      (node (ref "U701") (pin "42") (pinfunction "P9.0/TACLK/RTCCLK_42") (pintype "passive"))
    )
    (net (code "110") (name "unconnected-(U701-P9.1{slash}A5-Pad11)") (class "Default")
      (node (ref "U701") (pin "11") (pinfunction "P9.1/A5_11") (pintype "passive"))
    )
    (net (code "111") (name "unconnected-(U701-P9.2{slash}A4-Pad12)") (class "Default")
      (node (ref "U701") (pin "12") (pinfunction "P9.2/A4_12") (pintype "passive"))
    )
    (net (code "112") (name "unconnected-(U701-P9.3{slash}A3-Pad13)") (class "Default")
      (node (ref "U701") (pin "13") (pinfunction "P9.3/A3_13") (pintype "passive"))
    )
    (net (code "113") (name "unconnected-(U701-VREF-Pad7)") (class "Default")
      (node (ref "U701") (pin "7") (pinfunction "VREF_7") (pintype "passive"))
    )
  )
)
